# ME_433_HW3.net
KiCad netlist of a schematic drawn in EAGLE
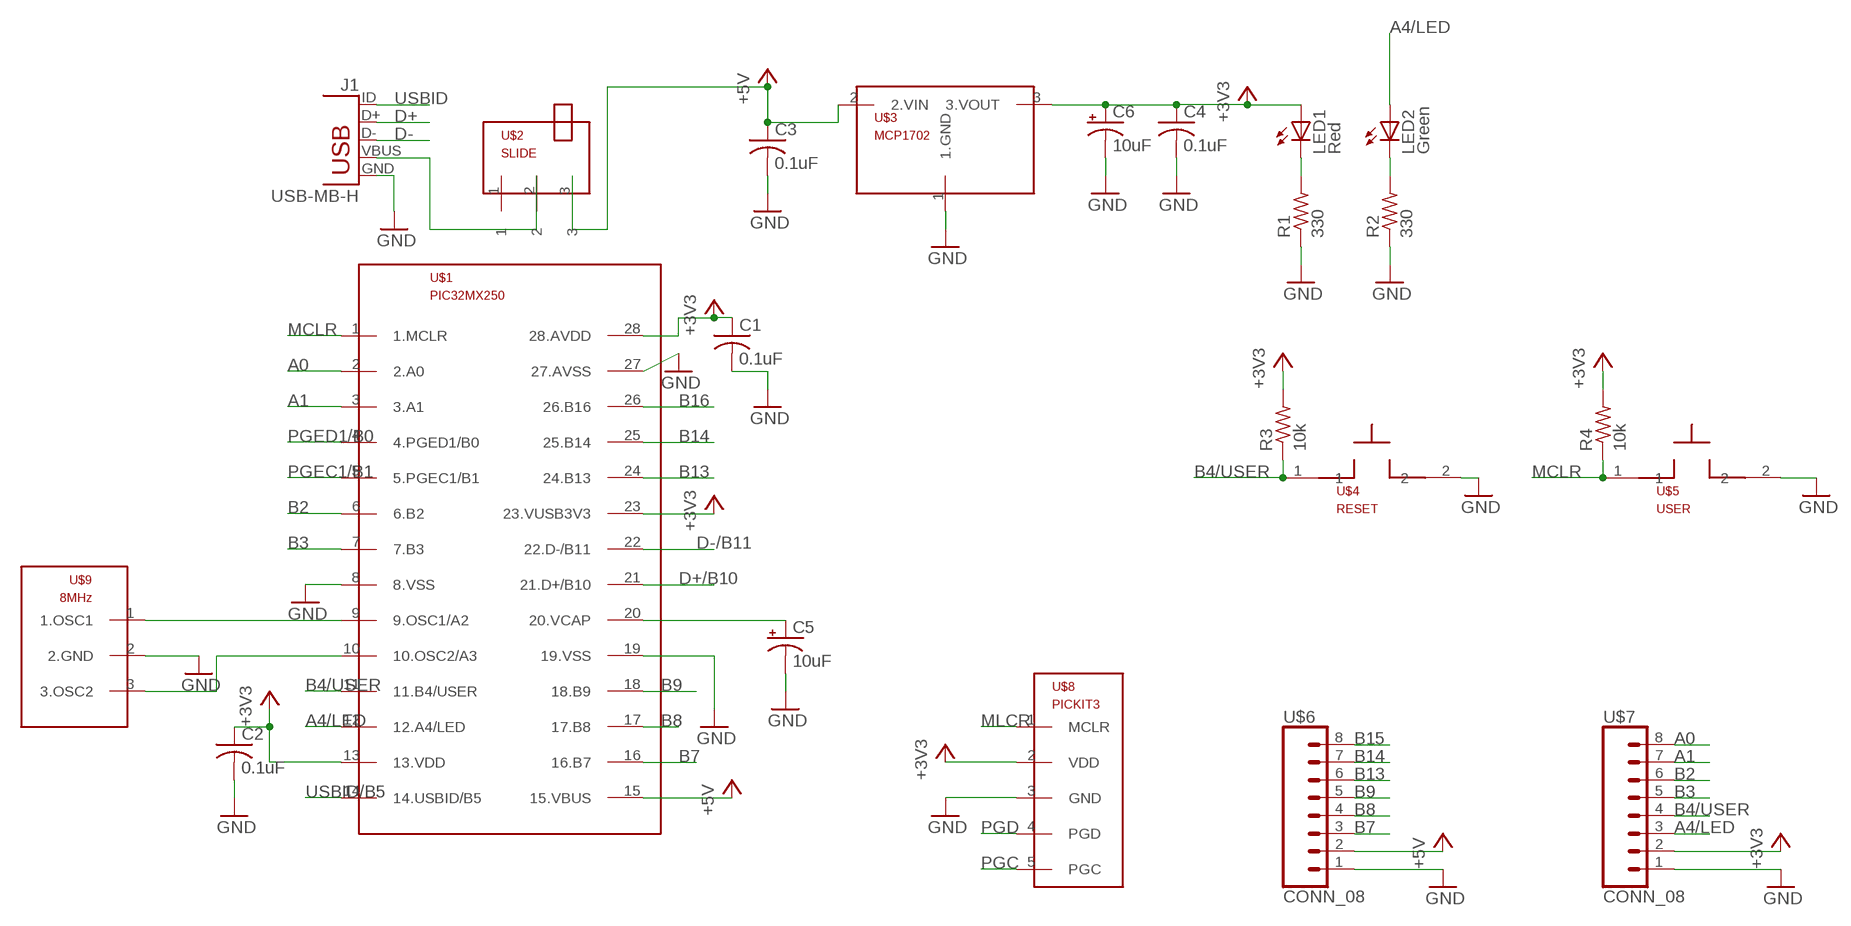
[diagram p0: schematic, sheet 1]

(export (version "E")
  (design (tool "Eeschema 10.0.6"))
  (components
    (comp (ref "C1")
      (value "0.1uF")
      (footprint "eagle-import:C025-025X050")
      (libsource (lib "eagle-import") (part "C-US025-025X050"))
    )
    (comp (ref "C2")
      (value "0.1uF")
      (footprint "eagle-import:C025-025X050")
      (libsource (lib "eagle-import") (part "C-US025-025X050"))
    )
    (comp (ref "C3")
      (value "0.1uF")
      (footprint "eagle-import:C025-025X050")
      (libsource (lib "eagle-import") (part "C-US025-025X050"))
    )
    (comp (ref "C4")
      (value "0.1uF")
      (footprint "eagle-import:C025-025X050")
      (libsource (lib "eagle-import") (part "C-US025-025X050"))
    )
    (comp (ref "C5")
      (value "10uF")
      (footprint "eagle-import:B45181B")
      (libsource (lib "eagle-import") (part "CPOL-USB45181B"))
    )
    (comp (ref "C6")
      (value "10uF")
      (footprint "eagle-import:B45181B")
      (libsource (lib "eagle-import") (part "CPOL-USB45181B"))
    )
    (comp (ref "J1")
      (value "USB-MB-H")
      (footprint "eagle-import:USB-MB-H")
      (libsource (lib "eagle-import") (part "USB-MB-H"))
    )
    (comp (ref "LED1")
      (value "Red")
      (footprint "eagle-import:LED3MM")
      (libsource (lib "eagle-import") (part "LED3MM"))
    )
    (comp (ref "LED2")
      (value "Green")
      (footprint "eagle-import:LED3MM")
      (libsource (lib "eagle-import") (part "LED3MM"))
    )
    (comp (ref "R1")
      (value "330")
      (footprint "eagle-import:0207_10")
      (libsource (lib "eagle-import") (part "R-US_0207/10"))
    )
    (comp (ref "R2")
      (value "330")
      (footprint "eagle-import:0207_10")
      (libsource (lib "eagle-import") (part "R-US_0207/10"))
    )
    (comp (ref "R3")
      (value "10k")
      (footprint "eagle-import:0207_10")
      (libsource (lib "eagle-import") (part "R-US_0207/10"))
    )
    (comp (ref "R4")
      (value "10k")
      (footprint "eagle-import:0207_10")
      (libsource (lib "eagle-import") (part "R-US_0207/10"))
    )
    (comp (ref "U$1")
      (value "PIC32MX250")
      (footprint "eagle-import:DIL28-3")
      (libsource (lib "eagle-import") (part "PIC32MX250"))
    )
    (comp (ref "U$2")
      (value "SLIDE")
      (footprint "eagle-import:SLIDE")
      (libsource (lib "eagle-import") (part "SLIDE"))
    )
    (comp (ref "U$3")
      (value "MCP1702")
      (footprint "eagle-import:TO92")
      (libsource (lib "eagle-import") (part "MCP1702"))
    )
    (comp (ref "U$4")
      (value "RESET")
      (footprint "eagle-import:PB")
      (libsource (lib "eagle-import") (part "PB"))
    )
    (comp (ref "U$5")
      (value "USER")
      (footprint "eagle-import:PB")
      (libsource (lib "eagle-import") (part "PB"))
    )
    (comp (ref "U$6")
      (value "CONN_08")
      (footprint "eagle-import:1X08")
      (libsource (lib "eagle-import") (part "CONN_08"))
    )
    (comp (ref "U$7")
      (value "CONN_08")
      (footprint "eagle-import:1X08")
      (libsource (lib "eagle-import") (part "CONN_08"))
    )
    (comp (ref "U$8")
      (value "PICKIT3")
      (footprint "eagle-import:1X05")
      (libsource (lib "eagle-import") (part "PICKIT3"))
    )
    (comp (ref "U$9")
      (value "8MHz")
      (footprint "eagle-import:OSC")
      (libsource (lib "eagle-import") (part "OSC"))
    )
  )
  (nets
    (net (code "1") (name "+3V3") (class "Default")
      (node (ref "C1") (pin "1") (pinfunction "1_1") (pintype "passive"))
      (node (ref "C2") (pin "1") (pinfunction "1_1") (pintype "passive"))
      (node (ref "C4") (pin "1") (pinfunction "1_1") (pintype "passive"))
      (node (ref "C6") (pin "+") (pinfunction "+_+") (pintype "passive"))
      (node (ref "LED1") (pin "A") (pinfunction "A_A") (pintype "passive"))
      (node (ref "R3") (pin "2") (pinfunction "2_2") (pintype "passive"))
      (node (ref "R4") (pin "2") (pinfunction "2_2") (pintype "passive"))
      (node (ref "U$1") (pin "13") (pinfunction "13.VDD_13") (pintype "bidirectional"))
      (node (ref "U$1") (pin "23") (pinfunction "23.VUSB3V3_23") (pintype "bidirectional"))
      (node (ref "U$1") (pin "28") (pinfunction "28.AVDD_28") (pintype "bidirectional"))
      (node (ref "U$3") (pin "3") (pinfunction "3.VOUT_3") (pintype "bidirectional"))
      (node (ref "U$7") (pin "2") (pinfunction "2_2") (pintype "passive"))
      (node (ref "U$8") (pin "2") (pinfunction "VDD_2") (pintype "bidirectional"))
    )
    (net (code "2") (name "+5V") (class "Default")
      (node (ref "C3") (pin "1") (pinfunction "1_1") (pintype "passive"))
      (node (ref "U$1") (pin "15") (pinfunction "15.VBUS_15") (pintype "bidirectional"))
      (node (ref "U$2") (pin "3") (pinfunction "3_3") (pintype "bidirectional"))
      (node (ref "U$3") (pin "2") (pinfunction "2.VIN_2") (pintype "bidirectional"))
      (node (ref "U$6") (pin "2") (pinfunction "2_2") (pintype "passive"))
    )
    (net (code "3") (name "/A0") (class "Default")
      (node (ref "U$1") (pin "2") (pinfunction "2.A0_2") (pintype "bidirectional"))
      (node (ref "U$7") (pin "8") (pinfunction "8_8") (pintype "passive"))
    )
    (net (code "4") (name "/A1") (class "Default")
      (node (ref "U$1") (pin "3") (pinfunction "3.A1_3") (pintype "bidirectional"))
      (node (ref "U$7") (pin "7") (pinfunction "7_7") (pintype "passive"))
    )
    (net (code "5") (name "/A4{slash}LED") (class "Default")
      (node (ref "LED2") (pin "A") (pinfunction "A_A") (pintype "passive"))
      (node (ref "U$1") (pin "12") (pinfunction "12.A4/LED_12") (pintype "bidirectional"))
      (node (ref "U$7") (pin "3") (pinfunction "3_3") (pintype "passive"))
    )
    (net (code "6") (name "/B2") (class "Default")
      (node (ref "U$1") (pin "6") (pinfunction "6.B2_6") (pintype "bidirectional"))
      (node (ref "U$7") (pin "6") (pinfunction "6_6") (pintype "passive"))
    )
    (net (code "7") (name "/B3") (class "Default")
      (node (ref "U$1") (pin "7") (pinfunction "7.B3_7") (pintype "bidirectional"))
      (node (ref "U$7") (pin "5") (pinfunction "5_5") (pintype "passive"))
    )
    (net (code "8") (name "/B4{slash}USER") (class "Default")
      (node (ref "R3") (pin "1") (pinfunction "1_1") (pintype "passive"))
      (node (ref "U$1") (pin "11") (pinfunction "11.B4/USER_11") (pintype "bidirectional"))
      (node (ref "U$4") (pin "1") (pinfunction "1_1") (pintype "bidirectional"))
      (node (ref "U$7") (pin "4") (pinfunction "4_4") (pintype "passive"))
    )
    (net (code "9") (name "/B7") (class "Default")
      (node (ref "U$1") (pin "16") (pinfunction "16.B7_16") (pintype "bidirectional"))
      (node (ref "U$6") (pin "3") (pinfunction "3_3") (pintype "passive"))
    )
    (net (code "10") (name "/B8") (class "Default")
      (node (ref "U$1") (pin "17") (pinfunction "17.B8_17") (pintype "bidirectional"))
      (node (ref "U$6") (pin "4") (pinfunction "4_4") (pintype "passive"))
    )
    (net (code "11") (name "/B9") (class "Default")
      (node (ref "U$1") (pin "18") (pinfunction "18.B9_18") (pintype "bidirectional"))
      (node (ref "U$6") (pin "5") (pinfunction "5_5") (pintype "passive"))
    )
    (net (code "12") (name "/B13") (class "Default")
      (node (ref "U$1") (pin "24") (pinfunction "24.B13_24") (pintype "bidirectional"))
      (node (ref "U$6") (pin "6") (pinfunction "6_6") (pintype "passive"))
    )
    (net (code "13") (name "/B14") (class "Default")
      (node (ref "U$1") (pin "25") (pinfunction "25.B14_25") (pintype "bidirectional"))
      (node (ref "U$6") (pin "7") (pinfunction "7_7") (pintype "passive"))
    )
    (net (code "14") (name "/B15") (class "Default")
      (node (ref "U$6") (pin "8") (pinfunction "8_8") (pintype "passive"))
    )
    (net (code "15") (name "/B16") (class "Default")
      (node (ref "U$1") (pin "26") (pinfunction "26.B16_26") (pintype "bidirectional"))
    )
    (net (code "16") (name "/D+") (class "Default")
      (node (ref "J1") (pin "D+") (pinfunction "D+_D+") (pintype "bidirectional"))
    )
    (net (code "17") (name "/D+{slash}B10") (class "Default")
      (node (ref "U$1") (pin "21") (pinfunction "21.D+/B10_21") (pintype "bidirectional"))
    )
    (net (code "18") (name "/D-") (class "Default")
      (node (ref "J1") (pin "D-") (pinfunction "D-_D-") (pintype "bidirectional"))
    )
    (net (code "19") (name "/D-{slash}B11") (class "Default")
      (node (ref "U$1") (pin "22") (pinfunction "22.D-/B11_22") (pintype "bidirectional"))
    )
    (net (code "20") (name "/MCLR") (class "Default")
      (node (ref "R4") (pin "1") (pinfunction "1_1") (pintype "passive"))
      (node (ref "U$1") (pin "1") (pinfunction "1.MCLR_1") (pintype "bidirectional"))
      (node (ref "U$5") (pin "1") (pinfunction "1_1") (pintype "bidirectional"))
    )
    (net (code "21") (name "/MLCR") (class "Default")
      (node (ref "U$8") (pin "1") (pinfunction "MCLR_1") (pintype "bidirectional"))
    )
    (net (code "22") (name "/PGC") (class "Default")
      (node (ref "U$8") (pin "5") (pinfunction "PGC_5") (pintype "bidirectional"))
    )
    (net (code "23") (name "/PGD") (class "Default")
      (node (ref "U$8") (pin "4") (pinfunction "PGD_4") (pintype "bidirectional"))
    )
    (net (code "24") (name "/PGEC1{slash}B1") (class "Default")
      (node (ref "U$1") (pin "5") (pinfunction "5.PGEC1/B1_5") (pintype "bidirectional"))
    )
    (net (code "25") (name "/PGED1{slash}B0") (class "Default")
      (node (ref "U$1") (pin "4") (pinfunction "4.PGED1/B0_4") (pintype "bidirectional"))
    )
    (net (code "26") (name "/USBID") (class "Default")
      (node (ref "J1") (pin "ID") (pinfunction "ID_ID") (pintype "bidirectional"))
    )
    (net (code "27") (name "/USBID{slash}B5") (class "Default")
      (node (ref "U$1") (pin "14") (pinfunction "14.USBID/B5_14") (pintype "bidirectional"))
    )
    (net (code "28") (name "GND") (class "Default")
      (node (ref "C1") (pin "2") (pinfunction "2_2") (pintype "passive"))
      (node (ref "C2") (pin "2") (pinfunction "2_2") (pintype "passive"))
      (node (ref "C3") (pin "2") (pinfunction "2_2") (pintype "passive"))
      (node (ref "C4") (pin "2") (pinfunction "2_2") (pintype "passive"))
      (node (ref "C5") (pin "-") (pinfunction "-_-") (pintype "passive"))
      (node (ref "C6") (pin "-") (pinfunction "-_-") (pintype "passive"))
      (node (ref "J1") (pin "GND") (pinfunction "GND_GND") (pintype "bidirectional"))
      (node (ref "R1") (pin "1") (pinfunction "1_1") (pintype "passive"))
      (node (ref "R2") (pin "1") (pinfunction "1_1") (pintype "passive"))
      (node (ref "U$1") (pin "19") (pinfunction "19.VSS_19") (pintype "bidirectional"))
      (node (ref "U$1") (pin "27") (pinfunction "27.AVSS_27") (pintype "bidirectional"))
      (node (ref "U$1") (pin "8") (pinfunction "8.VSS_8") (pintype "bidirectional"))
      (node (ref "U$3") (pin "1") (pinfunction "1.GND_1") (pintype "bidirectional"))
      (node (ref "U$4") (pin "2") (pinfunction "2_2") (pintype "bidirectional"))
      (node (ref "U$5") (pin "2") (pinfunction "2_2") (pintype "bidirectional"))
      (node (ref "U$6") (pin "1") (pinfunction "1_1") (pintype "passive"))
      (node (ref "U$7") (pin "1") (pinfunction "1_1") (pintype "passive"))
      (node (ref "U$8") (pin "3") (pinfunction "GND_3") (pintype "bidirectional"))
      (node (ref "U$9") (pin "2") (pinfunction "2.GND_2") (pintype "bidirectional"))
    )
    (net (code "29") (name "Net-(J1-PadVBUS)") (class "Default")
      (node (ref "J1") (pin "VBUS") (pinfunction "VBUS_VBUS") (pintype "bidirectional"))
      (node (ref "U$2") (pin "2") (pinfunction "2_2") (pintype "bidirectional"))
    )
    (net (code "30") (name "Net-(LED1-C)") (class "Default")
      (node (ref "LED1") (pin "K") (pinfunction "C_K") (pintype "passive"))
      (node (ref "R1") (pin "2") (pinfunction "2_2") (pintype "passive"))
    )
    (net (code "31") (name "Net-(LED2-C)") (class "Default")
      (node (ref "LED2") (pin "K") (pinfunction "C_K") (pintype "passive"))
      (node (ref "R2") (pin "2") (pinfunction "2_2") (pintype "passive"))
    )
    (net (code "32") (name "Net-(U$1-9.OSC1{slash}A2)") (class "Default")
      (node (ref "U$1") (pin "9") (pinfunction "9.OSC1/A2_9") (pintype "bidirectional"))
      (node (ref "U$9") (pin "1") (pinfunction "1.OSC1_1") (pintype "bidirectional"))
    )
    (net (code "33") (name "Net-(U$1-10.OSC2{slash}A3)") (class "Default")
      (node (ref "U$1") (pin "10") (pinfunction "10.OSC2/A3_10") (pintype "bidirectional"))
      (node (ref "U$9") (pin "3") (pinfunction "3.OSC2_3") (pintype "bidirectional"))
    )
    (net (code "34") (name "Net-(U$1-20.VCAP)") (class "Default")
      (node (ref "C5") (pin "+") (pinfunction "+_+") (pintype "passive"))
      (node (ref "U$1") (pin "20") (pinfunction "20.VCAP_20") (pintype "bidirectional"))
    )
    (net (code "35") (name "unconnected-(U$2-Pad1)") (class "Default")
      (node (ref "U$2") (pin "1") (pinfunction "1_1") (pintype "bidirectional"))
    )
  )
)
